# Robot_Omini.net
KiCad netlist of a schematic drawn in Altium Designer
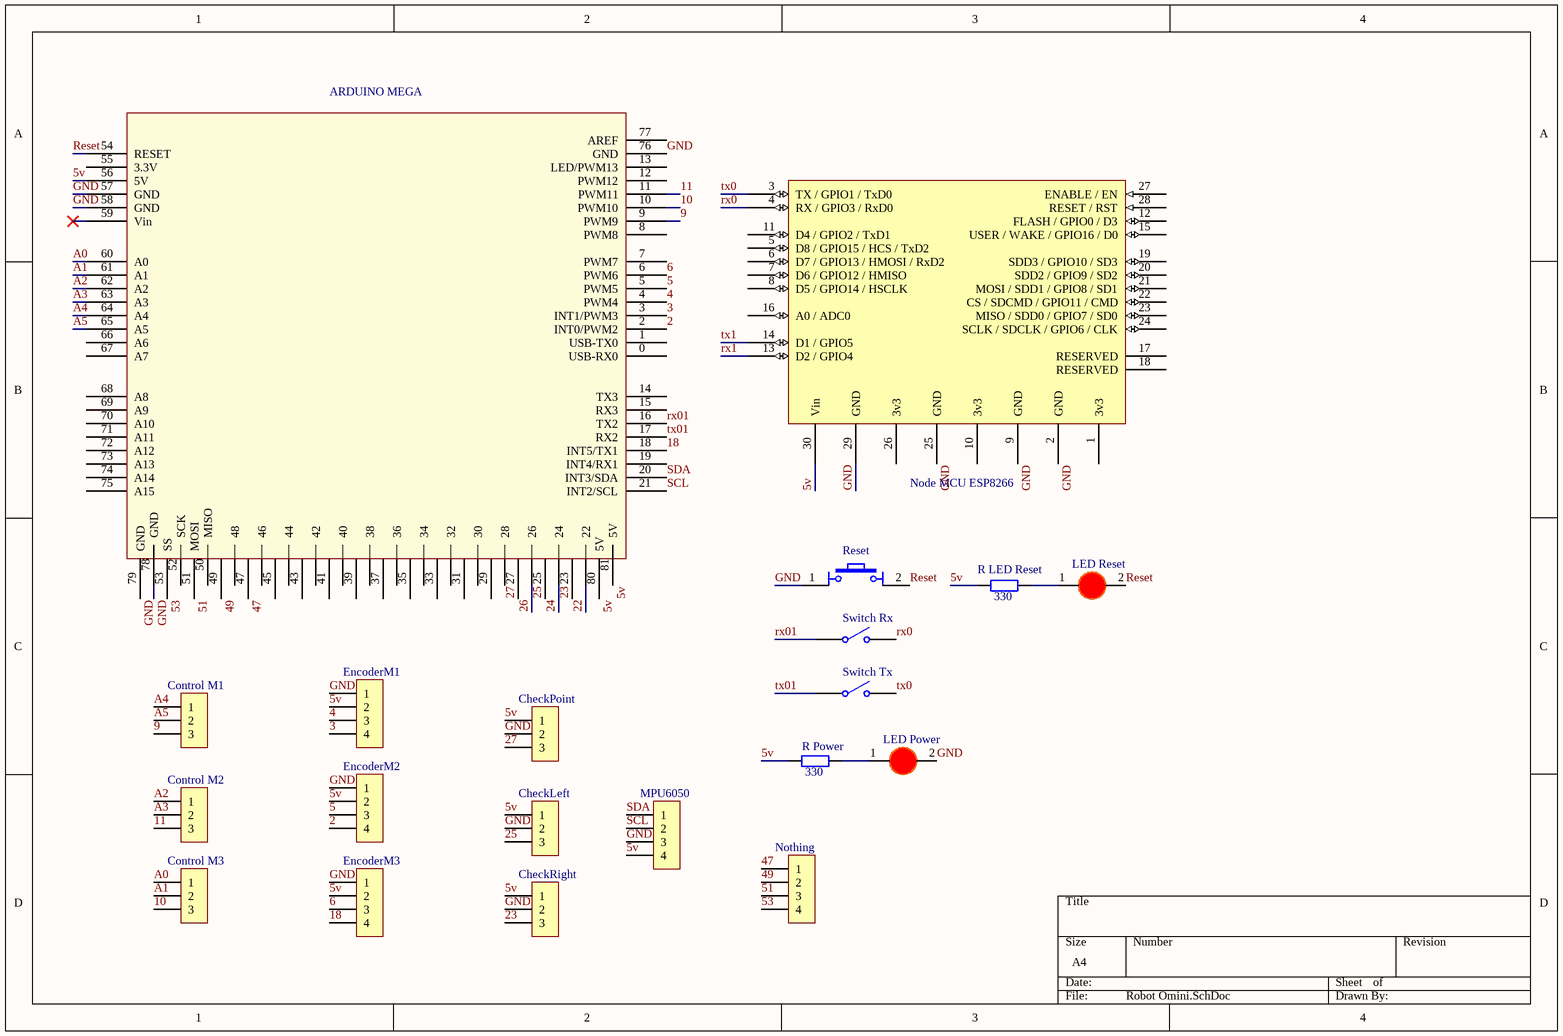
[diagram p0: Robot Omini.SchDoc]

(export (version "E")
  (design (tool "Eeschema 10.0.6"))
  (components
    (comp (ref "Arduino Mega")
      (value "ARDUINO MEGA")
      (footprint "ARDUINO MEGA")
      (libsource (lib "Arduino") (part "ARDUINO MEGA"))
    )
    (comp (ref "CheckLeft")
      (value "~")
      (footprint "Header DT 3P_2.54")
      (description "Cắm")
      (libsource (lib "Altium_Lib_by_KhueNguyenCreator") (part "Header 3P 2.54 Duc Thang"))
    )
    (comp (ref "CheckPoint")
      (value "~")
      (footprint "Header DT 3P_2.54")
      (description "Cắm")
      (libsource (lib "Altium_Lib_by_KhueNguyenCreator") (part "Header 3P 2.54 Duc Thang"))
    )
    (comp (ref "CheckRight")
      (value "~")
      (footprint "Header DT 3P_2.54")
      (description "Cắm")
      (libsource (lib "Altium_Lib_by_KhueNguyenCreator") (part "Header 3P 2.54 Duc Thang"))
    )
    (comp (ref "Control M1")
      (value "~")
      (footprint "Header DT 3P_2.54")
      (description "Cắm")
      (libsource (lib "Altium_Lib_by_KhueNguyenCreator") (part "Header 3P 2.54 Duc Thang"))
    )
    (comp (ref "Control M2")
      (value "~")
      (footprint "Header DT 3P_2.54")
      (description "Cắm")
      (libsource (lib "Altium_Lib_by_KhueNguyenCreator") (part "Header 3P 2.54 Duc Thang"))
    )
    (comp (ref "Control M3")
      (value "~")
      (footprint "Header DT 3P_2.54")
      (description "Cắm")
      (libsource (lib "Altium_Lib_by_KhueNguyenCreator") (part "Header 3P 2.54 Duc Thang"))
    )
    (comp (ref "EncoderM1")
      (value "Header 4P 2.54 Duc Thang")
      (footprint "Header DT 4P_2.54")
      (description "Cắm")
      (libsource (lib "Altium_Lib_by_KhueNguyenCreator") (part "Header 4P 2.54 Duc Thang"))
    )
    (comp (ref "EncoderM2")
      (value "Header 4P 2.54 Duc Thang")
      (footprint "Header DT 4P_2.54")
      (description "Cắm")
      (libsource (lib "Altium_Lib_by_KhueNguyenCreator") (part "Header 4P 2.54 Duc Thang"))
    )
    (comp (ref "EncoderM3")
      (value "Header 4P 2.54 Duc Thang")
      (footprint "Header DT 4P_2.54")
      (description "Cắm")
      (libsource (lib "Altium_Lib_by_KhueNguyenCreator") (part "Header 4P 2.54 Duc Thang"))
    )
    (comp (ref "LED Power")
      (value "LED 3mm")
      (footprint "LED-3MM-RED")
      (description "Cắm")
      (libsource (lib "Altium_Lib_by_KhueNguyenCreator") (part "LED 3mm Do"))
    )
    (comp (ref "LED Reset")
      (value "LED 3mm")
      (footprint "LED-3MM-RED")
      (description "Cắm")
      (libsource (lib "Altium_Lib_by_KhueNguyenCreator") (part "LED 3mm Do"))
    )
    (comp (ref "MPU6050")
      (value "Header 4P 2.54 Duc Thang")
      (footprint "Header DT 4P_2.54")
      (description "Cắm")
      (libsource (lib "Altium_Lib_by_KhueNguyenCreator") (part "Header 4P 2.54 Duc Thang"))
    )
    (comp (ref "NodeMCU")
      (value "Node MCU ESP8266")
      (footprint "NodeMCU DevKit v1.0 - Inside Labels")
      (libsource (lib "NodeMCU") (part "NodeMCU DevKit v1.0"))
    )
    (comp (ref "Nothing")
      (value "Header 4P 2.54 Duc Thang")
      (footprint "Header DT 4P_2.54")
      (description "Cắm")
      (libsource (lib "Altium_Lib_by_KhueNguyenCreator") (part "Header 4P 2.54 Duc Thang"))
    )
    (comp (ref "R LED Reset")
      (value "330")
      (footprint "tro vach 1/4w")
      (description "Cắm")
      (libsource (lib "Altium_Lib_by_KhueNguyenCreator") (part "Tro Vach 1/4W 5% 510R"))
    )
    (comp (ref "R Power")
      (value "330")
      (footprint "tro vach 1/4w")
      (description "Cắm")
      (libsource (lib "Altium_Lib_by_KhueNguyenCreator") (part "Tro Vach 1/4W 5% 510R"))
    )
    (comp (ref "Reset")
      (value "Nut Nhan 4 Chan Cam 6x6")
      (footprint "Nut Nhan 4 Chan Cam 6x6")
      (description "Nut Nhan 4 Chan 6x6mm")
      (libsource (lib "Altium_Lib_by_KhueNguyenCreator") (part "Nut Nhan 4 Chan Cam 6x6"))
    )
    (comp (ref "Switch Rx")
      (value "SW-SPST")
      (footprint "SPST-2")
      (description "Single-Pole, Single-Throw Switch")
      (fields (field (name "PUBLISHER") "Altium Limited"))
      (libsource (lib "Miscellaneous Devices") (part "SW-SPST"))
    )
    (comp (ref "Switch Tx")
      (value "SW-SPST")
      (footprint "SPST-2")
      (description "Single-Pole, Single-Throw Switch")
      (fields (field (name "PUBLISHER") "Altium Limited"))
      (libsource (lib "Miscellaneous Devices") (part "SW-SPST"))
    )
  )
  (nets
    (net (code "1") (name "/2") (class "Default")
      (node (ref "Arduino Mega") (pin "2") (pinfunction "INT0/PWM2_2") (pintype "passive"))
      (node (ref "EncoderM2") (pin "4") (pinfunction "4_4") (pintype "passive"))
    )
    (net (code "2") (name "/3") (class "Default")
      (node (ref "Arduino Mega") (pin "3") (pinfunction "INT1/PWM3_3") (pintype "passive"))
      (node (ref "EncoderM1") (pin "4") (pinfunction "4_4") (pintype "passive"))
    )
    (net (code "3") (name "/4") (class "Default")
      (node (ref "Arduino Mega") (pin "4") (pinfunction "PWM4_4") (pintype "passive"))
      (node (ref "EncoderM1") (pin "3") (pinfunction "3_3") (pintype "passive"))
    )
    (net (code "4") (name "/5") (class "Default")
      (node (ref "Arduino Mega") (pin "5") (pinfunction "PWM5_5") (pintype "passive"))
      (node (ref "EncoderM2") (pin "3") (pinfunction "3_3") (pintype "passive"))
    )
    (net (code "5") (name "/5v") (class "Default")
      (node (ref "Arduino Mega") (pin "56") (pinfunction "5V_56") (pintype "passive"))
      (node (ref "Arduino Mega") (pin "80") (pinfunction "5V_80") (pintype "passive"))
      (node (ref "Arduino Mega") (pin "81") (pinfunction "5V_81") (pintype "passive"))
      (node (ref "CheckLeft") (pin "1") (pinfunction "1_1") (pintype "passive"))
      (node (ref "CheckPoint") (pin "1") (pinfunction "1_1") (pintype "passive"))
      (node (ref "CheckRight") (pin "1") (pinfunction "1_1") (pintype "passive"))
      (node (ref "EncoderM1") (pin "2") (pinfunction "2_2") (pintype "passive"))
      (node (ref "EncoderM2") (pin "2") (pinfunction "2_2") (pintype "passive"))
      (node (ref "EncoderM3") (pin "2") (pinfunction "2_2") (pintype "passive"))
      (node (ref "MPU6050") (pin "4") (pinfunction "4_4") (pintype "passive"))
      (node (ref "NodeMCU") (pin "30") (pinfunction "Vin_30") (pintype "passive"))
      (node (ref "R LED Reset") (pin "1") (pinfunction "1_1") (pintype "passive"))
      (node (ref "R Power") (pin "1") (pinfunction "1_1") (pintype "passive"))
    )
    (net (code "6") (name "/6") (class "Default")
      (node (ref "Arduino Mega") (pin "6") (pinfunction "PWM6_6") (pintype "passive"))
      (node (ref "EncoderM3") (pin "3") (pinfunction "3_3") (pintype "passive"))
    )
    (net (code "7") (name "/9") (class "Default")
      (node (ref "Arduino Mega") (pin "9") (pinfunction "PWM9_9") (pintype "passive"))
      (node (ref "Control M1") (pin "3") (pinfunction "3_3") (pintype "passive"))
    )
    (net (code "8") (name "/10") (class "Default")
      (node (ref "Arduino Mega") (pin "10") (pinfunction "PWM10_10") (pintype "passive"))
      (node (ref "Control M3") (pin "3") (pinfunction "3_3") (pintype "passive"))
    )
    (net (code "9") (name "/11") (class "Default")
      (node (ref "Arduino Mega") (pin "11") (pinfunction "PWM11_11") (pintype "passive"))
      (node (ref "Control M2") (pin "3") (pinfunction "3_3") (pintype "passive"))
    )
    (net (code "10") (name "/18") (class "Default")
      (node (ref "Arduino Mega") (pin "18") (pinfunction "INT5/TX1_18") (pintype "passive"))
      (node (ref "EncoderM3") (pin "4") (pinfunction "4_4") (pintype "passive"))
    )
    (net (code "11") (name "/22") (class "Default")
      (node (ref "Arduino Mega") (pin "22") (pinfunction "22_22") (pintype "passive"))
    )
    (net (code "12") (name "/23") (class "Default")
      (node (ref "Arduino Mega") (pin "23") (pinfunction "23_23") (pintype "passive"))
      (node (ref "CheckRight") (pin "3") (pinfunction "3_3") (pintype "passive"))
    )
    (net (code "13") (name "/24") (class "Default")
      (node (ref "Arduino Mega") (pin "24") (pinfunction "24_24") (pintype "passive"))
    )
    (net (code "14") (name "/25") (class "Default")
      (node (ref "Arduino Mega") (pin "25") (pinfunction "25_25") (pintype "passive"))
      (node (ref "CheckLeft") (pin "3") (pinfunction "3_3") (pintype "passive"))
    )
    (net (code "15") (name "/26") (class "Default")
      (node (ref "Arduino Mega") (pin "26") (pinfunction "26_26") (pintype "passive"))
    )
    (net (code "16") (name "/27") (class "Default")
      (node (ref "Arduino Mega") (pin "27") (pinfunction "27_27") (pintype "passive"))
      (node (ref "CheckPoint") (pin "3") (pinfunction "3_3") (pintype "passive"))
    )
    (net (code "17") (name "/47") (class "Default")
      (node (ref "Arduino Mega") (pin "47") (pinfunction "47_47") (pintype "passive"))
      (node (ref "Nothing") (pin "1") (pinfunction "1_1") (pintype "passive"))
    )
    (net (code "18") (name "/49") (class "Default")
      (node (ref "Arduino Mega") (pin "49") (pinfunction "49_49") (pintype "passive"))
      (node (ref "Nothing") (pin "2") (pinfunction "2_2") (pintype "passive"))
    )
    (net (code "19") (name "/51") (class "Default")
      (node (ref "Arduino Mega") (pin "51") (pinfunction "MOSI_51") (pintype "passive"))
      (node (ref "Nothing") (pin "3") (pinfunction "3_3") (pintype "passive"))
    )
    (net (code "20") (name "/53") (class "Default")
      (node (ref "Arduino Mega") (pin "53") (pinfunction "SS_53") (pintype "passive"))
      (node (ref "Nothing") (pin "4") (pinfunction "4_4") (pintype "passive"))
    )
    (net (code "21") (name "/A0") (class "Default")
      (node (ref "Arduino Mega") (pin "60") (pinfunction "A0_60") (pintype "passive"))
      (node (ref "Control M3") (pin "1") (pinfunction "1_1") (pintype "passive"))
    )
    (net (code "22") (name "/A1") (class "Default")
      (node (ref "Arduino Mega") (pin "61") (pinfunction "A1_61") (pintype "passive"))
      (node (ref "Control M3") (pin "2") (pinfunction "2_2") (pintype "passive"))
    )
    (net (code "23") (name "/A2") (class "Default")
      (node (ref "Arduino Mega") (pin "62") (pinfunction "A2_62") (pintype "passive"))
      (node (ref "Control M2") (pin "1") (pinfunction "1_1") (pintype "passive"))
    )
    (net (code "24") (name "/A3") (class "Default")
      (node (ref "Arduino Mega") (pin "63") (pinfunction "A3_63") (pintype "passive"))
      (node (ref "Control M2") (pin "2") (pinfunction "2_2") (pintype "passive"))
    )
    (net (code "25") (name "/A4") (class "Default")
      (node (ref "Arduino Mega") (pin "64") (pinfunction "A4_64") (pintype "passive"))
      (node (ref "Control M1") (pin "1") (pinfunction "1_1") (pintype "passive"))
    )
    (net (code "26") (name "/A5") (class "Default")
      (node (ref "Arduino Mega") (pin "65") (pinfunction "A5_65") (pintype "passive"))
      (node (ref "Control M1") (pin "2") (pinfunction "2_2") (pintype "passive"))
    )
    (net (code "27") (name "/GND") (class "Default")
      (node (ref "Arduino Mega") (pin "57") (pinfunction "GND_57") (pintype "passive"))
      (node (ref "Arduino Mega") (pin "58") (pinfunction "GND_58") (pintype "passive"))
      (node (ref "Arduino Mega") (pin "76") (pinfunction "GND_76") (pintype "passive"))
      (node (ref "Arduino Mega") (pin "78") (pinfunction "GND_78") (pintype "passive"))
      (node (ref "Arduino Mega") (pin "79") (pinfunction "GND_79") (pintype "passive"))
      (node (ref "CheckLeft") (pin "2") (pinfunction "2_2") (pintype "passive"))
      (node (ref "CheckPoint") (pin "2") (pinfunction "2_2") (pintype "passive"))
      (node (ref "CheckRight") (pin "2") (pinfunction "2_2") (pintype "passive"))
      (node (ref "EncoderM1") (pin "1") (pinfunction "1_1") (pintype "passive"))
      (node (ref "EncoderM2") (pin "1") (pinfunction "1_1") (pintype "passive"))
      (node (ref "EncoderM3") (pin "1") (pinfunction "1_1") (pintype "passive"))
      (node (ref "LED Power") (pin "2") (pinfunction "K_2") (pintype "passive"))
      (node (ref "MPU6050") (pin "3") (pinfunction "3_3") (pintype "passive"))
      (node (ref "NodeMCU") (pin "2") (pinfunction "GND_2") (pintype "power_in"))
      (node (ref "NodeMCU") (pin "25") (pinfunction "GND_25") (pintype "power_in"))
      (node (ref "NodeMCU") (pin "29") (pinfunction "GND_29") (pintype "passive"))
      (node (ref "NodeMCU") (pin "9") (pinfunction "GND_9") (pintype "power_in"))
      (node (ref "Reset") (pin "1") (pintype "passive"))
    )
    (net (code "28") (name "/Reset") (class "Default")
      (node (ref "Arduino Mega") (pin "54") (pinfunction "RESET_54") (pintype "passive"))
      (node (ref "LED Reset") (pin "2") (pinfunction "K_2") (pintype "passive"))
      (node (ref "Reset") (pin "2") (pintype "passive"))
    )
    (net (code "29") (name "/SCL") (class "Default")
      (node (ref "Arduino Mega") (pin "21") (pinfunction "INT2/SCL_21") (pintype "passive"))
      (node (ref "MPU6050") (pin "2") (pinfunction "2_2") (pintype "passive"))
    )
    (net (code "30") (name "/SDA") (class "Default")
      (node (ref "Arduino Mega") (pin "20") (pinfunction "INT3/SDA_20") (pintype "passive"))
      (node (ref "MPU6050") (pin "1") (pinfunction "1_1") (pintype "passive"))
    )
    (net (code "31") (name "/rx0") (class "Default")
      (node (ref "NodeMCU") (pin "4") (pinfunction "RX_/_GPIO3_/_RxD0_4") (pintype "bidirectional"))
      (node (ref "Switch Rx") (pin "2") (pinfunction "NO_2") (pintype "passive"))
    )
    (net (code "32") (name "/rx01") (class "Default")
      (node (ref "Arduino Mega") (pin "16") (pinfunction "TX2_16") (pintype "passive"))
      (node (ref "Switch Rx") (pin "1") (pinfunction "COMMON_1") (pintype "passive"))
    )
    (net (code "33") (name "/rx1") (class "Default")
      (node (ref "NodeMCU") (pin "13") (pinfunction "D2_/_GPIO4_13") (pintype "bidirectional"))
    )
    (net (code "34") (name "/tx0") (class "Default")
      (node (ref "NodeMCU") (pin "3") (pinfunction "TX_/_GPIO1_/_TxD0_3") (pintype "bidirectional"))
      (node (ref "Switch Tx") (pin "2") (pinfunction "NO_2") (pintype "passive"))
    )
    (net (code "35") (name "/tx01") (class "Default")
      (node (ref "Arduino Mega") (pin "17") (pinfunction "RX2_17") (pintype "passive"))
      (node (ref "Switch Tx") (pin "1") (pinfunction "COMMON_1") (pintype "passive"))
    )
    (net (code "36") (name "/tx1") (class "Default")
      (node (ref "NodeMCU") (pin "14") (pinfunction "D1_/_GPIO5_14") (pintype "bidirectional"))
    )
    (net (code "37") (name "Net-(LED Power-A)") (class "Default")
      (node (ref "LED Power") (pin "1") (pinfunction "A_1") (pintype "passive"))
      (node (ref "R Power") (pin "2") (pinfunction "2_2") (pintype "passive"))
    )
    (net (code "38") (name "Net-(LED Reset-A)") (class "Default")
      (node (ref "LED Reset") (pin "1") (pinfunction "A_1") (pintype "passive"))
      (node (ref "R LED Reset") (pin "2") (pinfunction "2_2") (pintype "passive"))
    )
    (net (code "39") (name "unconnected-(Arduino Mega-3.3V-Pad55)") (class "Default")
      (node (ref "Arduino Mega") (pin "55") (pinfunction "3.3V_55") (pintype "passive"))
    )
    (net (code "40") (name "unconnected-(Arduino Mega-A6-Pad66)") (class "Default")
      (node (ref "Arduino Mega") (pin "66") (pinfunction "A6_66") (pintype "passive"))
    )
    (net (code "41") (name "unconnected-(Arduino Mega-A7-Pad67)") (class "Default")
      (node (ref "Arduino Mega") (pin "67") (pinfunction "A7_67") (pintype "passive"))
    )
    (net (code "42") (name "unconnected-(Arduino Mega-A8-Pad68)") (class "Default")
      (node (ref "Arduino Mega") (pin "68") (pinfunction "A8_68") (pintype "passive"))
    )
    (net (code "43") (name "unconnected-(Arduino Mega-A9-Pad69)") (class "Default")
      (node (ref "Arduino Mega") (pin "69") (pinfunction "A9_69") (pintype "passive"))
    )
    (net (code "44") (name "unconnected-(Arduino Mega-A10-Pad70)") (class "Default")
      (node (ref "Arduino Mega") (pin "70") (pinfunction "A10_70") (pintype "passive"))
    )
    (net (code "45") (name "unconnected-(Arduino Mega-A11-Pad71)") (class "Default")
      (node (ref "Arduino Mega") (pin "71") (pinfunction "A11_71") (pintype "passive"))
    )
    (net (code "46") (name "unconnected-(Arduino Mega-A12-Pad72)") (class "Default")
      (node (ref "Arduino Mega") (pin "72") (pinfunction "A12_72") (pintype "passive"))
    )
    (net (code "47") (name "unconnected-(Arduino Mega-A13-Pad73)") (class "Default")
      (node (ref "Arduino Mega") (pin "73") (pinfunction "A13_73") (pintype "passive"))
    )
    (net (code "48") (name "unconnected-(Arduino Mega-A14-Pad74)") (class "Default")
      (node (ref "Arduino Mega") (pin "74") (pinfunction "A14_74") (pintype "passive"))
    )
    (net (code "49") (name "unconnected-(Arduino Mega-A15-Pad75)") (class "Default")
      (node (ref "Arduino Mega") (pin "75") (pinfunction "A15_75") (pintype "passive"))
    )
    (net (code "50") (name "unconnected-(Arduino Mega-AREF-Pad77)") (class "Default")
      (node (ref "Arduino Mega") (pin "77") (pinfunction "AREF_77") (pintype "passive"))
    )
    (net (code "51") (name "unconnected-(Arduino Mega-INT4{slash}RX1-Pad19)") (class "Default")
      (node (ref "Arduino Mega") (pin "19") (pinfunction "INT4/RX1_19") (pintype "passive"))
    )
    (net (code "52") (name "unconnected-(Arduino Mega-LED{slash}PWM13-Pad13)") (class "Default")
      (node (ref "Arduino Mega") (pin "13") (pinfunction "LED/PWM13_13") (pintype "passive"))
    )
    (net (code "53") (name "unconnected-(Arduino Mega-MISO-Pad50)") (class "Default")
      (node (ref "Arduino Mega") (pin "50") (pinfunction "MISO_50") (pintype "passive"))
    )
    (net (code "54") (name "unconnected-(Arduino Mega-PWM7-Pad7)") (class "Default")
      (node (ref "Arduino Mega") (pin "7") (pinfunction "PWM7_7") (pintype "passive"))
    )
    (net (code "55") (name "unconnected-(Arduino Mega-PWM8-Pad8)") (class "Default")
      (node (ref "Arduino Mega") (pin "8") (pinfunction "PWM8_8") (pintype "passive"))
    )
    (net (code "56") (name "unconnected-(Arduino Mega-PWM12-Pad12)") (class "Default")
      (node (ref "Arduino Mega") (pin "12") (pinfunction "PWM12_12") (pintype "passive"))
    )
    (net (code "57") (name "unconnected-(Arduino Mega-Pad28)") (class "Default")
      (node (ref "Arduino Mega") (pin "28") (pinfunction "28_28") (pintype "passive"))
    )
    (net (code "58") (name "unconnected-(Arduino Mega-Pad29)") (class "Default")
      (node (ref "Arduino Mega") (pin "29") (pinfunction "29_29") (pintype "passive"))
    )
    (net (code "59") (name "unconnected-(Arduino Mega-Pad30)") (class "Default")
      (node (ref "Arduino Mega") (pin "30") (pinfunction "30_30") (pintype "passive"))
    )
    (net (code "60") (name "unconnected-(Arduino Mega-Pad31)") (class "Default")
      (node (ref "Arduino Mega") (pin "31") (pinfunction "31_31") (pintype "passive"))
    )
    (net (code "61") (name "unconnected-(Arduino Mega-Pad32)") (class "Default")
      (node (ref "Arduino Mega") (pin "32") (pinfunction "32_32") (pintype "passive"))
    )
    (net (code "62") (name "unconnected-(Arduino Mega-Pad33)") (class "Default")
      (node (ref "Arduino Mega") (pin "33") (pinfunction "33_33") (pintype "passive"))
    )
    (net (code "63") (name "unconnected-(Arduino Mega-Pad34)") (class "Default")
      (node (ref "Arduino Mega") (pin "34") (pinfunction "34_34") (pintype "passive"))
    )
    (net (code "64") (name "unconnected-(Arduino Mega-Pad35)") (class "Default")
      (node (ref "Arduino Mega") (pin "35") (pinfunction "35_35") (pintype "passive"))
    )
    (net (code "65") (name "unconnected-(Arduino Mega-Pad36)") (class "Default")
      (node (ref "Arduino Mega") (pin "36") (pinfunction "36_36") (pintype "passive"))
    )
    (net (code "66") (name "unconnected-(Arduino Mega-Pad37)") (class "Default")
      (node (ref "Arduino Mega") (pin "37") (pinfunction "37_37") (pintype "passive"))
    )
    (net (code "67") (name "unconnected-(Arduino Mega-Pad38)") (class "Default")
      (node (ref "Arduino Mega") (pin "38") (pinfunction "38_38") (pintype "passive"))
    )
    (net (code "68") (name "unconnected-(Arduino Mega-Pad39)") (class "Default")
      (node (ref "Arduino Mega") (pin "39") (pinfunction "39_39") (pintype "passive"))
    )
    (net (code "69") (name "unconnected-(Arduino Mega-Pad40)") (class "Default")
      (node (ref "Arduino Mega") (pin "40") (pinfunction "40_40") (pintype "passive"))
    )
    (net (code "70") (name "unconnected-(Arduino Mega-Pad41)") (class "Default")
      (node (ref "Arduino Mega") (pin "41") (pinfunction "41_41") (pintype "passive"))
    )
    (net (code "71") (name "unconnected-(Arduino Mega-Pad42)") (class "Default")
      (node (ref "Arduino Mega") (pin "42") (pinfunction "42_42") (pintype "passive"))
    )
    (net (code "72") (name "unconnected-(Arduino Mega-Pad43)") (class "Default")
      (node (ref "Arduino Mega") (pin "43") (pinfunction "43_43") (pintype "passive"))
    )
    (net (code "73") (name "unconnected-(Arduino Mega-Pad44)") (class "Default")
      (node (ref "Arduino Mega") (pin "44") (pinfunction "44_44") (pintype "passive"))
    )
    (net (code "74") (name "unconnected-(Arduino Mega-Pad45)") (class "Default")
      (node (ref "Arduino Mega") (pin "45") (pinfunction "45_45") (pintype "passive"))
    )
    (net (code "75") (name "unconnected-(Arduino Mega-Pad46)") (class "Default")
      (node (ref "Arduino Mega") (pin "46") (pinfunction "46_46") (pintype "passive"))
    )
    (net (code "76") (name "unconnected-(Arduino Mega-Pad48)") (class "Default")
      (node (ref "Arduino Mega") (pin "48") (pinfunction "48_48") (pintype "passive"))
    )
    (net (code "77") (name "unconnected-(Arduino Mega-RX3-Pad15)") (class "Default")
      (node (ref "Arduino Mega") (pin "15") (pinfunction "RX3_15") (pintype "passive"))
    )
    (net (code "78") (name "unconnected-(Arduino Mega-SCK-Pad52)") (class "Default")
      (node (ref "Arduino Mega") (pin "52") (pinfunction "SCK_52") (pintype "passive"))
    )
    (net (code "79") (name "unconnected-(Arduino Mega-TX3-Pad14)") (class "Default")
      (node (ref "Arduino Mega") (pin "14") (pinfunction "TX3_14") (pintype "passive"))
    )
    (net (code "80") (name "unconnected-(Arduino Mega-USB-RX0-Pad0)") (class "Default")
      (node (ref "Arduino Mega") (pin "0") (pinfunction "USB-RX0_0") (pintype "passive"))
    )
    (net (code "81") (name "unconnected-(Arduino Mega-USB-TX0-Pad1)") (class "Default")
      (node (ref "Arduino Mega") (pin "1") (pinfunction "USB-TX0_1") (pintype "passive"))
    )
    (net (code "82") (name "unconnected-(Arduino Mega-Vin-Pad59)") (class "Default")
      (node (ref "Arduino Mega") (pin "59") (pinfunction "Vin_59") (pintype "passive+no_connect"))
    )
    (net (code "83") (name "unconnected-(NodeMCU-3v3-Pad1)") (class "Default")
      (node (ref "NodeMCU") (pin "1") (pinfunction "3v3_1") (pintype "power_in"))
    )
    (net (code "84") (name "unconnected-(NodeMCU-3v3-Pad10)") (class "Default")
      (node (ref "NodeMCU") (pin "10") (pinfunction "3v3_10") (pintype "power_in"))
    )
    (net (code "85") (name "unconnected-(NodeMCU-3v3-Pad26)") (class "Default")
      (node (ref "NodeMCU") (pin "26") (pinfunction "3v3_26") (pintype "power_in"))
    )
    (net (code "86") (name "unconnected-(NodeMCU-A0_{slash}_ADC0-Pad16)") (class "Default")
      (node (ref "NodeMCU") (pin "16") (pinfunction "A0_/_ADC0_16") (pintype "bidirectional"))
    )
    (net (code "87") (name "unconnected-(NodeMCU-CS_{slash}_SDCMD_{slash}_GPIO11_{slash}_CMD-Pad22)") (class "Default")
      (node (ref "NodeMCU") (pin "22") (pinfunction "CS_/_SDCMD_/_GPIO11_/_CMD_22") (pintype "bidirectional"))
    )
    (net (code "88") (name "unconnected-(NodeMCU-D4_{slash}_GPIO2_{slash}_TxD1-Pad11)") (class "Default")
      (node (ref "NodeMCU") (pin "11") (pinfunction "D4_/_GPIO2_/_TxD1_11") (pintype "bidirectional"))
    )
    (net (code "89") (name "unconnected-(NodeMCU-D5_{slash}_GPIO14_{slash}_HSCLK-Pad8)") (class "Default")
      (node (ref "NodeMCU") (pin "8") (pinfunction "D5_/_GPIO14_/_HSCLK_8") (pintype "bidirectional"))
    )
    (net (code "90") (name "unconnected-(NodeMCU-D6_{slash}_GPIO12_{slash}_HMISO-Pad7)") (class "Default")
      (node (ref "NodeMCU") (pin "7") (pinfunction "D6_/_GPIO12_/_HMISO_7") (pintype "bidirectional"))
    )
    (net (code "91") (name "unconnected-(NodeMCU-D7_{slash}_GPIO13_{slash}_HMOSI_{slash}_RxD2-Pad6)") (class "Default")
      (node (ref "NodeMCU") (pin "6") (pinfunction "D7_/_GPIO13_/_HMOSI_/_RxD2_6") (pintype "bidirectional"))
    )
    (net (code "92") (name "unconnected-(NodeMCU-D8_{slash}_GPIO15_{slash}_HCS_{slash}_TxD2-Pad5)") (class "Default")
      (node (ref "NodeMCU") (pin "5") (pinfunction "D8_/_GPIO15_/_HCS_/_TxD2_5") (pintype "bidirectional"))
    )
    (net (code "93") (name "unconnected-(NodeMCU-ENABLE_{slash}_EN-Pad27)") (class "Default")
      (node (ref "NodeMCU") (pin "27") (pinfunction "ENABLE_/_EN_27") (pintype "input"))
    )
    (net (code "94") (name "unconnected-(NodeMCU-FLASH_{slash}_GPIO0_{slash}_D3-Pad12)") (class "Default")
      (node (ref "NodeMCU") (pin "12") (pinfunction "FLASH_/_GPIO0_/_D3_12") (pintype "bidirectional"))
    )
    (net (code "95") (name "unconnected-(NodeMCU-MISO_{slash}_SDD0_{slash}_GPIO7_{slash}_SD0-Pad23)") (class "Default")
      (node (ref "NodeMCU") (pin "23") (pinfunction "MISO_/_SDD0_/_GPIO7_/_SD0_23") (pintype "bidirectional"))
    )
    (net (code "96") (name "unconnected-(NodeMCU-MOSI_{slash}_SDD1_{slash}_GPIO8_{slash}_SD1-Pad21)") (class "Default")
      (node (ref "NodeMCU") (pin "21") (pinfunction "MOSI_/_SDD1_/_GPIO8_/_SD1_21") (pintype "bidirectional"))
    )
    (net (code "97") (name "unconnected-(NodeMCU-RESERVED-Pad17)") (class "Default")
      (node (ref "NodeMCU") (pin "17") (pinfunction "RESERVED_17") (pintype "passive"))
    )
    (net (code "98") (name "unconnected-(NodeMCU-RESERVED-Pad18)") (class "Default")
      (node (ref "NodeMCU") (pin "18") (pinfunction "RESERVED_18") (pintype "passive"))
    )
    (net (code "99") (name "unconnected-(NodeMCU-RESET_{slash}_RST-Pad28)") (class "Default")
      (node (ref "NodeMCU") (pin "28") (pinfunction "RESET_/_RST_28") (pintype "input"))
    )
    (net (code "100") (name "unconnected-(NodeMCU-SCLK_{slash}_SDCLK_{slash}_GPIO6_{slash}_CLK-Pad24)") (class "Default")
      (node (ref "NodeMCU") (pin "24") (pinfunction "SCLK_/_SDCLK_/_GPIO6_/_CLK_24") (pintype "bidirectional"))
    )
    (net (code "101") (name "unconnected-(NodeMCU-SDD2_{slash}_GPIO9_{slash}_SD2-Pad20)") (class "Default")
      (node (ref "NodeMCU") (pin "20") (pinfunction "SDD2_/_GPIO9_/_SD2_20") (pintype "bidirectional"))
    )
    (net (code "102") (name "unconnected-(NodeMCU-SDD3_{slash}_GPIO10_{slash}_SD3-Pad19)") (class "Default")
      (node (ref "NodeMCU") (pin "19") (pinfunction "SDD3_/_GPIO10_/_SD3_19") (pintype "bidirectional"))
    )
    (net (code "103") (name "unconnected-(NodeMCU-USER_{slash}_WAKE_{slash}_GPIO16_{slash}_D0-Pad15)") (class "Default")
      (node (ref "NodeMCU") (pin "15") (pinfunction "USER_/_WAKE_/_GPIO16_/_D0_15") (pintype "bidirectional"))
    )
  )
)
